# Graduation_Project.net
KiCad netlist of a schematic drawn in EAGLE
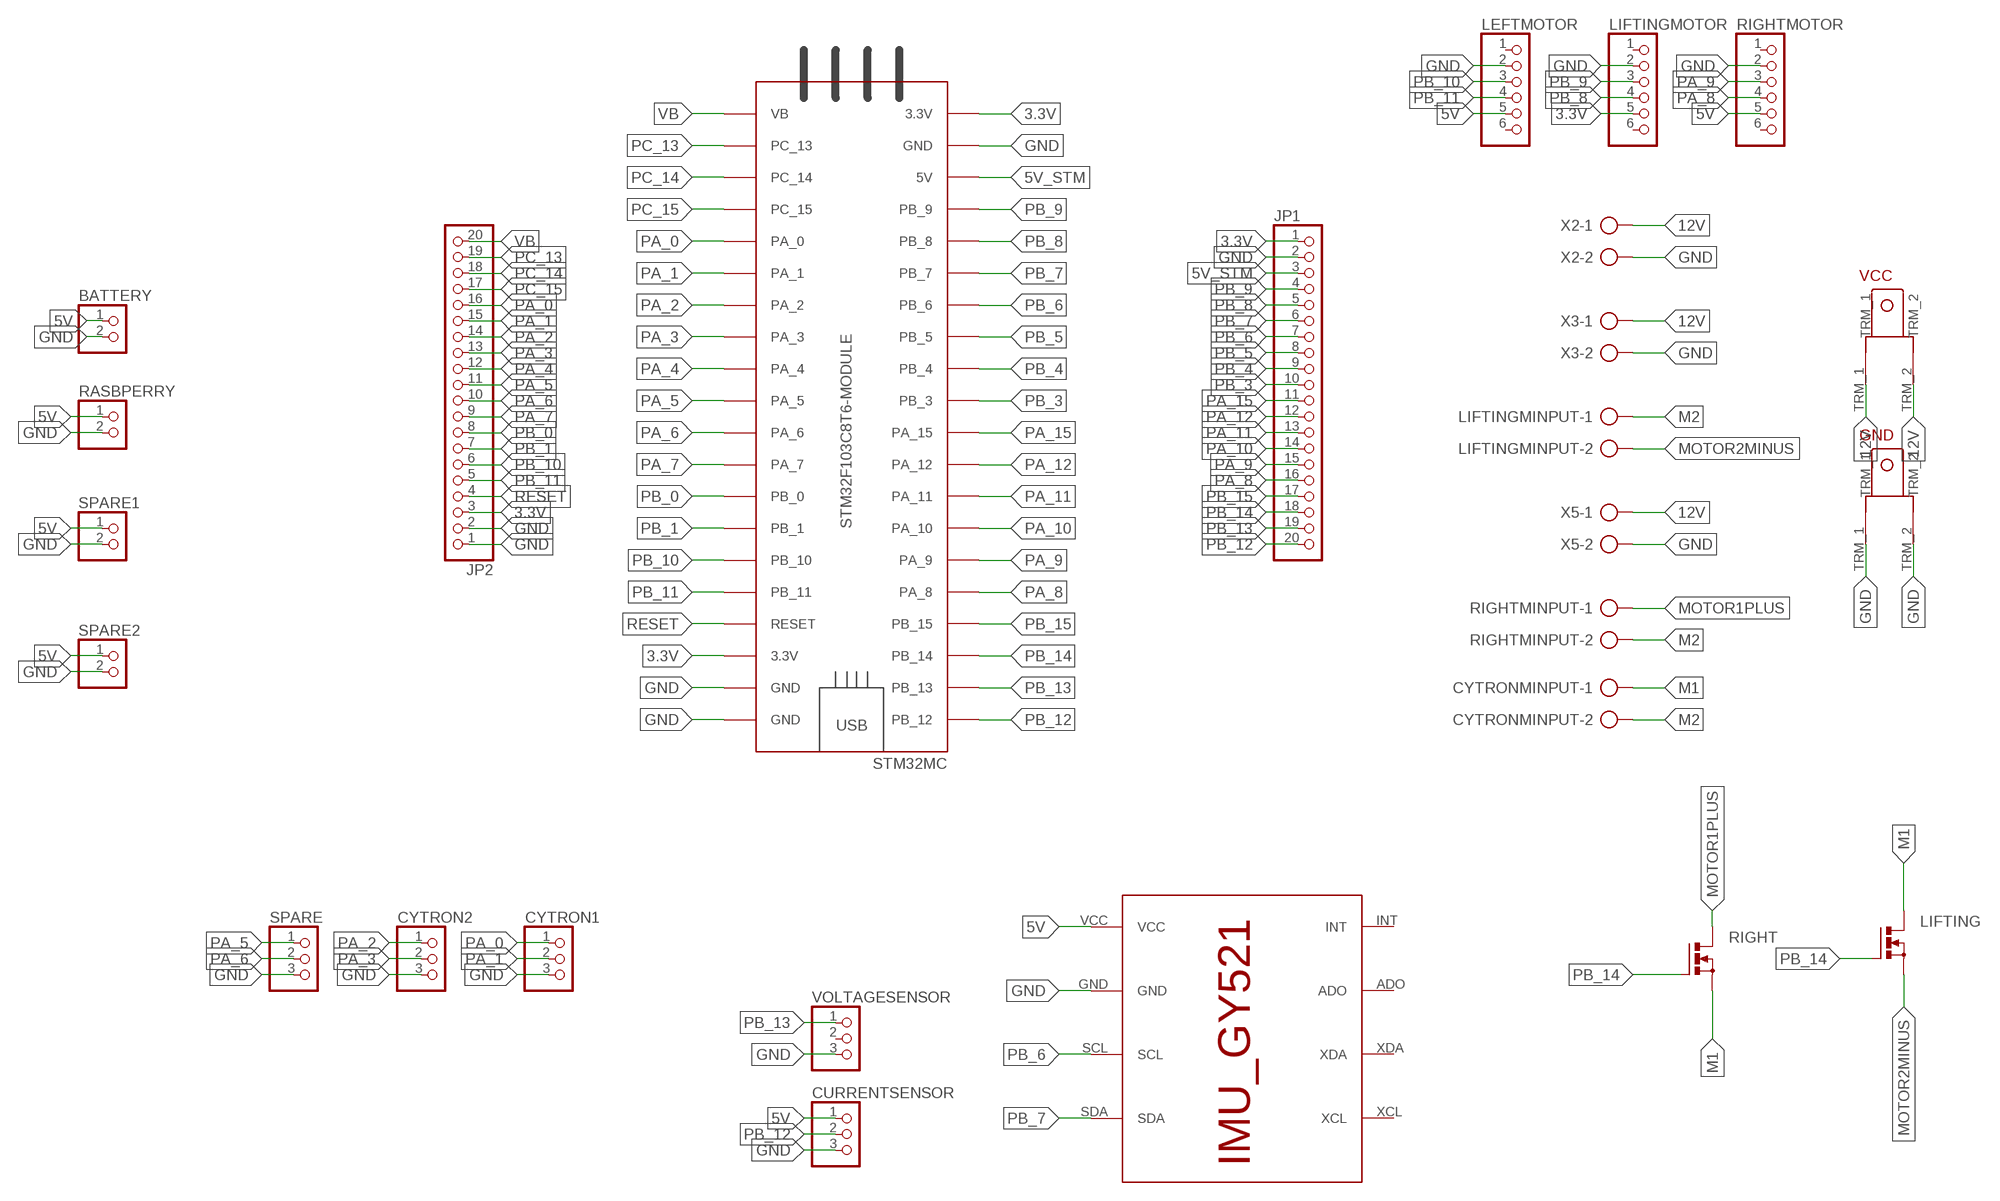
[diagram p0: schematic, sheet 1]

(export (version "E")
  (design (tool "Eeschema 10.0.6"))
  (components
    (comp (ref "BATTERY")
      (value "PINHD-1X2")
      (footprint "eagle-import:1X02")
      (libsource (lib "eagle-import") (part "PINHD-1X2"))
    )
    (comp (ref "CURRENTSENSOR")
      (value "PINHD-1X3")
      (footprint "eagle-import:1X03")
      (libsource (lib "eagle-import") (part "PINHD-1X3"))
    )
    (comp (ref "CYTRON1")
      (value "PINHD-1X3")
      (footprint "eagle-import:1X03")
      (libsource (lib "eagle-import") (part "PINHD-1X3"))
    )
    (comp (ref "CYTRON2")
      (value "PINHD-1X3")
      (footprint "eagle-import:1X03")
      (libsource (lib "eagle-import") (part "PINHD-1X3"))
    )
    (comp (ref "CYTRONMINPUT")
      (value "AK300/2")
      (footprint "eagle-import:AK300_2")
      (libsource (lib "eagle-import") (part "AK300/2"))
    )
    (comp (ref "GND")
      (value "TERMINAL_EDITED")
      (footprint "eagle-import:TERMINAL_EDITED")
      (libsource (lib "eagle-import") (part "TERMINAL_EDITED"))
    )
    (comp (ref "JP1")
      (value "PINHD-1X20")
      (footprint "eagle-import:1X20")
      (libsource (lib "eagle-import") (part "PINHD-1X20"))
    )
    (comp (ref "JP2")
      (value "PINHD-1X20")
      (footprint "eagle-import:1X20")
      (libsource (lib "eagle-import") (part "PINHD-1X20"))
    )
    (comp (ref "LEFTMOTOR")
      (value "PINHD-1X6")
      (footprint "eagle-import:1X06")
      (libsource (lib "eagle-import") (part "PINHD-1X6"))
    )
    (comp (ref "LIFTING")
      (value "MOSFET_NTO220BH")
      (footprint "eagle-import:TO220BH")
      (libsource (lib "eagle-import") (part "MOSFET_NTO220BH"))
    )
    (comp (ref "LIFTINGMINPUT")
      (value "AK300/2")
      (footprint "eagle-import:AK300_2")
      (libsource (lib "eagle-import") (part "AK300/2"))
    )
    (comp (ref "LIFTINGMOTOR")
      (value "PINHD-1X6")
      (footprint "eagle-import:1X06")
      (libsource (lib "eagle-import") (part "PINHD-1X6"))
    )
    (comp (ref "RASBPERRY")
      (value "PINHD-1X2")
      (footprint "eagle-import:1X02")
      (libsource (lib "eagle-import") (part "PINHD-1X2"))
    )
    (comp (ref "RIGHT")
      (value "MOSFET_NTO220BH")
      (footprint "eagle-import:TO220BH")
      (libsource (lib "eagle-import") (part "MOSFET_NTO220BH"))
    )
    (comp (ref "RIGHTMINPUT")
      (value "AK300/2")
      (footprint "eagle-import:AK300_2")
      (libsource (lib "eagle-import") (part "AK300/2"))
    )
    (comp (ref "RIGHTMOTOR")
      (value "PINHD-1X6")
      (footprint "eagle-import:1X06")
      (libsource (lib "eagle-import") (part "PINHD-1X6"))
    )
    (comp (ref "SPARE")
      (value "PINHD-1X3")
      (footprint "eagle-import:1X03")
      (libsource (lib "eagle-import") (part "PINHD-1X3"))
    )
    (comp (ref "SPARE1")
      (value "PINHD-1X2")
      (footprint "eagle-import:1X02")
      (libsource (lib "eagle-import") (part "PINHD-1X2"))
    )
    (comp (ref "SPARE2")
      (value "PINHD-1X2")
      (footprint "eagle-import:1X02")
      (libsource (lib "eagle-import") (part "PINHD-1X2"))
    )
    (comp (ref "STM32MC")
      (value "STM32F103C8T6-MODULE")
      (footprint "eagle-import:STM32F103C8T6-MODULE")
      (libsource (lib "eagle-import") (part "STM32F103C8T6-MODULE"))
    )
    (comp (ref "U$1")
      (value "IMU_ROBOCON_GY521")
      (footprint "eagle-import:IMU_GY521")
      (libsource (lib "eagle-import") (part "IMU_ROBOCON_GY521"))
    )
    (comp (ref "VCC")
      (value "TERMINAL_EDITED")
      (footprint "eagle-import:TERMINAL_EDITED")
      (libsource (lib "eagle-import") (part "TERMINAL_EDITED"))
    )
    (comp (ref "VOLTAGESENSOR")
      (value "PINHD-1X3")
      (footprint "eagle-import:1X03")
      (libsource (lib "eagle-import") (part "PINHD-1X3"))
    )
    (comp (ref "X2")
      (value "AK300/2")
      (footprint "eagle-import:AK300_2")
      (libsource (lib "eagle-import") (part "AK300/2"))
    )
    (comp (ref "X3")
      (value "AK300/2")
      (footprint "eagle-import:AK300_2")
      (libsource (lib "eagle-import") (part "AK300/2"))
    )
    (comp (ref "X5")
      (value "AK300/2")
      (footprint "eagle-import:AK300_2")
      (libsource (lib "eagle-import") (part "AK300/2"))
    )
  )
  (nets
    (net (code "1") (name "3.3V") (class "Default")
      (node (ref "JP1") (pin "1") (pinfunction "1_1") (pintype "passive"))
      (node (ref "JP2") (pin "3") (pinfunction "3_3") (pintype "passive"))
      (node (ref "LIFTINGMOTOR") (pin "5") (pinfunction "5_5") (pintype "passive"))
      (node (ref "STM32MC") (pin "3.3V_1") (pinfunction "3.3V_3.3V_1") (pintype "bidirectional"))
      (node (ref "STM32MC") (pin "3.3V_2") (pinfunction "3.3V_3.3V_2") (pintype "bidirectional"))
    )
    (net (code "2") (name "5V") (class "Default")
      (node (ref "BATTERY") (pin "1") (pinfunction "1_1") (pintype "passive"))
      (node (ref "CURRENTSENSOR") (pin "1") (pinfunction "1_1") (pintype "passive"))
      (node (ref "LEFTMOTOR") (pin "5") (pinfunction "5_5") (pintype "passive"))
      (node (ref "RASBPERRY") (pin "1") (pinfunction "1_1") (pintype "passive"))
      (node (ref "RIGHTMOTOR") (pin "5") (pinfunction "5_5") (pintype "passive"))
      (node (ref "SPARE1") (pin "1") (pinfunction "1_1") (pintype "passive"))
      (node (ref "SPARE2") (pin "1") (pinfunction "1_1") (pintype "passive"))
      (node (ref "U$1") (pin "VCC") (pinfunction "VCC_VCC") (pintype "bidirectional"))
    )
    (net (code "3") (name "5V_STM") (class "Default")
      (node (ref "JP1") (pin "3") (pinfunction "3_3") (pintype "passive"))
      (node (ref "STM32MC") (pin "5V") (pinfunction "5V_5V") (pintype "bidirectional"))
    )
    (net (code "4") (name "12V") (class "Default")
      (node (ref "VCC") (pin "TRM_1") (pinfunction "TRM_1_TRM_1") (pintype "bidirectional"))
      (node (ref "VCC") (pin "TRM_2") (pinfunction "TRM_2_TRM_2") (pintype "bidirectional"))
      (node (ref "X2") (pin "1") (pinfunction "KL_1") (pintype "passive"))
      (node (ref "X3") (pin "1") (pinfunction "KL_1") (pintype "passive"))
      (node (ref "X5") (pin "1") (pinfunction "KL_1") (pintype "passive"))
    )
    (net (code "5") (name "GND") (class "Default")
      (node (ref "BATTERY") (pin "2") (pinfunction "2_2") (pintype "passive"))
      (node (ref "CURRENTSENSOR") (pin "3") (pinfunction "3_3") (pintype "passive"))
      (node (ref "CYTRON1") (pin "3") (pinfunction "3_3") (pintype "passive"))
      (node (ref "CYTRON2") (pin "3") (pinfunction "3_3") (pintype "passive"))
      (node (ref "GND") (pin "TRM_1") (pinfunction "TRM_1_TRM_1") (pintype "bidirectional"))
      (node (ref "GND") (pin "TRM_2") (pinfunction "TRM_2_TRM_2") (pintype "bidirectional"))
      (node (ref "JP1") (pin "2") (pinfunction "2_2") (pintype "passive"))
      (node (ref "JP2") (pin "1") (pinfunction "1_1") (pintype "passive"))
      (node (ref "JP2") (pin "2") (pinfunction "2_2") (pintype "passive"))
      (node (ref "LEFTMOTOR") (pin "2") (pinfunction "2_2") (pintype "passive"))
      (node (ref "LIFTINGMOTOR") (pin "2") (pinfunction "2_2") (pintype "passive"))
      (node (ref "RASBPERRY") (pin "2") (pinfunction "2_2") (pintype "passive"))
      (node (ref "RIGHTMOTOR") (pin "2") (pinfunction "2_2") (pintype "passive"))
      (node (ref "SPARE") (pin "3") (pinfunction "3_3") (pintype "passive"))
      (node (ref "SPARE1") (pin "2") (pinfunction "2_2") (pintype "passive"))
      (node (ref "SPARE2") (pin "2") (pinfunction "2_2") (pintype "passive"))
      (node (ref "STM32MC") (pin "GND_1") (pinfunction "GND_GND_1") (pintype "bidirectional"))
      (node (ref "STM32MC") (pin "GND_2") (pinfunction "GND_GND_2") (pintype "bidirectional"))
      (node (ref "STM32MC") (pin "GND_3") (pinfunction "GND_GND_3") (pintype "power_in"))
      (node (ref "U$1") (pin "GND") (pinfunction "GND_GND") (pintype "bidirectional"))
      (node (ref "VOLTAGESENSOR") (pin "3") (pinfunction "3_3") (pintype "passive"))
      (node (ref "X2") (pin "2") (pinfunction "KL_2") (pintype "passive"))
      (node (ref "X3") (pin "2") (pinfunction "KL_2") (pintype "passive"))
      (node (ref "X5") (pin "2") (pinfunction "KL_2") (pintype "passive"))
    )
    (net (code "6") (name "M1") (class "Default")
      (node (ref "CYTRONMINPUT") (pin "1") (pinfunction "KL_1") (pintype "passive"))
      (node (ref "LIFTING") (pin "D") (pinfunction "D_D") (pintype "passive"))
      (node (ref "RIGHT") (pin "S") (pinfunction "S_S") (pintype "passive"))
    )
    (net (code "7") (name "M2") (class "Default")
      (node (ref "CYTRONMINPUT") (pin "2") (pinfunction "KL_2") (pintype "passive"))
      (node (ref "LIFTINGMINPUT") (pin "1") (pinfunction "KL_1") (pintype "passive"))
      (node (ref "RIGHTMINPUT") (pin "2") (pinfunction "KL_2") (pintype "passive"))
    )
    (net (code "8") (name "MOTOR1PLUS") (class "Default")
      (node (ref "RIGHT") (pin "D") (pinfunction "D_D") (pintype "passive"))
      (node (ref "RIGHTMINPUT") (pin "1") (pinfunction "KL_1") (pintype "passive"))
    )
    (net (code "9") (name "MOTOR2MINUS") (class "Default")
      (node (ref "LIFTING") (pin "S") (pinfunction "S_S") (pintype "passive"))
      (node (ref "LIFTINGMINPUT") (pin "2") (pinfunction "KL_2") (pintype "passive"))
    )
    (net (code "10") (name "PA_0") (class "Default")
      (node (ref "CYTRON1") (pin "1") (pinfunction "1_1") (pintype "passive"))
      (node (ref "JP2") (pin "16") (pinfunction "16_16") (pintype "passive"))
      (node (ref "STM32MC") (pin "PA_0") (pinfunction "PA_0_PA_0") (pintype "bidirectional"))
    )
    (net (code "11") (name "PA_1") (class "Default")
      (node (ref "CYTRON1") (pin "2") (pinfunction "2_2") (pintype "passive"))
      (node (ref "JP2") (pin "15") (pinfunction "15_15") (pintype "passive"))
      (node (ref "STM32MC") (pin "PA_1") (pinfunction "PA_1_PA_1") (pintype "bidirectional"))
    )
    (net (code "12") (name "PA_2") (class "Default")
      (node (ref "CYTRON2") (pin "1") (pinfunction "1_1") (pintype "passive"))
      (node (ref "JP2") (pin "14") (pinfunction "14_14") (pintype "passive"))
      (node (ref "STM32MC") (pin "PA_2") (pinfunction "PA_2_PA_2") (pintype "bidirectional"))
    )
    (net (code "13") (name "PA_3") (class "Default")
      (node (ref "CYTRON2") (pin "2") (pinfunction "2_2") (pintype "passive"))
      (node (ref "JP2") (pin "13") (pinfunction "13_13") (pintype "passive"))
      (node (ref "STM32MC") (pin "PA_3") (pinfunction "PA_3_PA_3") (pintype "bidirectional"))
    )
    (net (code "14") (name "PA_4") (class "Default")
      (node (ref "JP2") (pin "12") (pinfunction "12_12") (pintype "passive"))
      (node (ref "STM32MC") (pin "PA_4") (pinfunction "PA_4_PA_4") (pintype "bidirectional"))
    )
    (net (code "15") (name "PA_5") (class "Default")
      (node (ref "JP2") (pin "11") (pinfunction "11_11") (pintype "passive"))
      (node (ref "SPARE") (pin "1") (pinfunction "1_1") (pintype "passive"))
      (node (ref "STM32MC") (pin "PA_5") (pinfunction "PA_5_PA_5") (pintype "bidirectional"))
    )
    (net (code "16") (name "PA_6") (class "Default")
      (node (ref "JP2") (pin "10") (pinfunction "10_10") (pintype "passive"))
      (node (ref "SPARE") (pin "2") (pinfunction "2_2") (pintype "passive"))
      (node (ref "STM32MC") (pin "PA_6") (pinfunction "PA_6_PA_6") (pintype "bidirectional"))
    )
    (net (code "17") (name "PA_7") (class "Default")
      (node (ref "JP2") (pin "9") (pinfunction "9_9") (pintype "passive"))
      (node (ref "STM32MC") (pin "PA_7") (pinfunction "PA_7_PA_7") (pintype "bidirectional"))
    )
    (net (code "18") (name "PA_8") (class "Default")
      (node (ref "JP1") (pin "16") (pinfunction "16_16") (pintype "passive"))
      (node (ref "RIGHTMOTOR") (pin "4") (pinfunction "4_4") (pintype "passive"))
      (node (ref "STM32MC") (pin "PA_8") (pinfunction "PA_8_PA_8") (pintype "bidirectional"))
    )
    (net (code "19") (name "PA_9") (class "Default")
      (node (ref "JP1") (pin "15") (pinfunction "15_15") (pintype "passive"))
      (node (ref "RIGHTMOTOR") (pin "3") (pinfunction "3_3") (pintype "passive"))
      (node (ref "STM32MC") (pin "PA_9") (pinfunction "PA_9_PA_9") (pintype "bidirectional"))
    )
    (net (code "20") (name "PA_10") (class "Default")
      (node (ref "JP1") (pin "14") (pinfunction "14_14") (pintype "passive"))
      (node (ref "STM32MC") (pin "PA_10") (pinfunction "PA_10_PA_10") (pintype "bidirectional"))
    )
    (net (code "21") (name "PA_11") (class "Default")
      (node (ref "JP1") (pin "13") (pinfunction "13_13") (pintype "passive"))
      (node (ref "STM32MC") (pin "PA_11") (pinfunction "PA_11_PA_11") (pintype "bidirectional"))
    )
    (net (code "22") (name "PA_12") (class "Default")
      (node (ref "JP1") (pin "12") (pinfunction "12_12") (pintype "passive"))
      (node (ref "STM32MC") (pin "PA_12") (pinfunction "PA_12_PA_12") (pintype "bidirectional"))
    )
    (net (code "23") (name "PA_15") (class "Default")
      (node (ref "JP1") (pin "11") (pinfunction "11_11") (pintype "passive"))
      (node (ref "STM32MC") (pin "PA_15") (pinfunction "PA_15_PA_15") (pintype "bidirectional"))
    )
    (net (code "24") (name "PB_0") (class "Default")
      (node (ref "JP2") (pin "8") (pinfunction "8_8") (pintype "passive"))
      (node (ref "STM32MC") (pin "PB_0") (pinfunction "PB_0_PB_0") (pintype "bidirectional"))
    )
    (net (code "25") (name "PB_1") (class "Default")
      (node (ref "JP2") (pin "7") (pinfunction "7_7") (pintype "passive"))
      (node (ref "STM32MC") (pin "PB_1") (pinfunction "PB_1_PB_1") (pintype "bidirectional"))
    )
    (net (code "26") (name "PB_3") (class "Default")
      (node (ref "JP1") (pin "10") (pinfunction "10_10") (pintype "passive"))
      (node (ref "STM32MC") (pin "PB_3") (pinfunction "PB_3_PB_3") (pintype "bidirectional"))
    )
    (net (code "27") (name "PB_4") (class "Default")
      (node (ref "JP1") (pin "9") (pinfunction "9_9") (pintype "passive"))
      (node (ref "STM32MC") (pin "PB_4") (pinfunction "PB_4_PB_4") (pintype "bidirectional"))
    )
    (net (code "28") (name "PB_5") (class "Default")
      (node (ref "JP1") (pin "8") (pinfunction "8_8") (pintype "passive"))
      (node (ref "STM32MC") (pin "PB_5") (pinfunction "PB_5_PB_5") (pintype "bidirectional"))
    )
    (net (code "29") (name "PB_6") (class "Default")
      (node (ref "JP1") (pin "7") (pinfunction "7_7") (pintype "passive"))
      (node (ref "STM32MC") (pin "PB_6") (pinfunction "PB_6_PB_6") (pintype "bidirectional"))
      (node (ref "U$1") (pin "SCL") (pinfunction "SCL_SCL") (pintype "bidirectional"))
    )
    (net (code "30") (name "PB_7") (class "Default")
      (node (ref "JP1") (pin "6") (pinfunction "6_6") (pintype "passive"))
      (node (ref "STM32MC") (pin "PB_7") (pinfunction "PB_7_PB_7") (pintype "bidirectional"))
      (node (ref "U$1") (pin "SDA") (pinfunction "SDA_SDA") (pintype "bidirectional"))
    )
    (net (code "31") (name "PB_8") (class "Default")
      (node (ref "JP1") (pin "5") (pinfunction "5_5") (pintype "passive"))
      (node (ref "LIFTINGMOTOR") (pin "4") (pinfunction "4_4") (pintype "passive"))
      (node (ref "STM32MC") (pin "PB_8") (pinfunction "PB_8_PB_8") (pintype "bidirectional"))
    )
    (net (code "32") (name "PB_9") (class "Default")
      (node (ref "JP1") (pin "4") (pinfunction "4_4") (pintype "passive"))
      (node (ref "LIFTINGMOTOR") (pin "3") (pinfunction "3_3") (pintype "passive"))
      (node (ref "STM32MC") (pin "PB_9") (pinfunction "PB_9_PB_9") (pintype "bidirectional"))
    )
    (net (code "33") (name "PB_10") (class "Default")
      (node (ref "JP2") (pin "6") (pinfunction "6_6") (pintype "passive"))
      (node (ref "LEFTMOTOR") (pin "3") (pinfunction "3_3") (pintype "passive"))
      (node (ref "STM32MC") (pin "PB_10") (pinfunction "PB_10_PB_10") (pintype "bidirectional"))
    )
    (net (code "34") (name "PB_11") (class "Default")
      (node (ref "JP2") (pin "5") (pinfunction "5_5") (pintype "passive"))
      (node (ref "LEFTMOTOR") (pin "4") (pinfunction "4_4") (pintype "passive"))
      (node (ref "STM32MC") (pin "PB_11") (pinfunction "PB_11_PB_11") (pintype "bidirectional"))
    )
    (net (code "35") (name "PB_12") (class "Default")
      (node (ref "CURRENTSENSOR") (pin "2") (pinfunction "2_2") (pintype "passive"))
      (node (ref "JP1") (pin "20") (pinfunction "20_20") (pintype "passive"))
      (node (ref "STM32MC") (pin "PB_12") (pinfunction "PB_12_PB_12") (pintype "bidirectional"))
    )
    (net (code "36") (name "PB_13") (class "Default")
      (node (ref "JP1") (pin "19") (pinfunction "19_19") (pintype "passive"))
      (node (ref "STM32MC") (pin "PB_13") (pinfunction "PB_13_PB_13") (pintype "bidirectional"))
      (node (ref "VOLTAGESENSOR") (pin "1") (pinfunction "1_1") (pintype "passive"))
    )
    (net (code "37") (name "PB_14") (class "Default")
      (node (ref "JP1") (pin "18") (pinfunction "18_18") (pintype "passive"))
      (node (ref "LIFTING") (pin "G") (pinfunction "G_G") (pintype "passive"))
      (node (ref "RIGHT") (pin "G") (pinfunction "G_G") (pintype "passive"))
      (node (ref "STM32MC") (pin "PB_14") (pinfunction "PB_14_PB_14") (pintype "bidirectional"))
    )
    (net (code "38") (name "PB_15") (class "Default")
      (node (ref "JP1") (pin "17") (pinfunction "17_17") (pintype "passive"))
      (node (ref "STM32MC") (pin "PB_15") (pinfunction "PB_15_PB_15") (pintype "bidirectional"))
    )
    (net (code "39") (name "PC_13") (class "Default")
      (node (ref "JP2") (pin "19") (pinfunction "19_19") (pintype "passive"))
      (node (ref "STM32MC") (pin "PC_13") (pinfunction "PC_13_PC_13") (pintype "bidirectional"))
    )
    (net (code "40") (name "PC_14") (class "Default")
      (node (ref "JP2") (pin "18") (pinfunction "18_18") (pintype "passive"))
      (node (ref "STM32MC") (pin "PC_14") (pinfunction "PC_14_PC_14") (pintype "bidirectional"))
    )
    (net (code "41") (name "PC_15") (class "Default")
      (node (ref "JP2") (pin "17") (pinfunction "17_17") (pintype "passive"))
      (node (ref "STM32MC") (pin "PC_15") (pinfunction "PC_15_PC_15") (pintype "bidirectional"))
    )
    (net (code "42") (name "RESET") (class "Default")
      (node (ref "JP2") (pin "4") (pinfunction "4_4") (pintype "passive"))
      (node (ref "STM32MC") (pin "RESET") (pinfunction "RESET_RESET") (pintype "bidirectional"))
    )
    (net (code "43") (name "VB") (class "Default")
      (node (ref "JP2") (pin "20") (pinfunction "20_20") (pintype "passive"))
      (node (ref "STM32MC") (pin "VB") (pinfunction "VB_VB") (pintype "bidirectional"))
    )
    (net (code "44") (name "unconnected-(LEFTMOTOR-Pad1)") (class "Default")
      (node (ref "LEFTMOTOR") (pin "1") (pinfunction "1_1") (pintype "passive"))
    )
    (net (code "45") (name "unconnected-(LEFTMOTOR-Pad6)") (class "Default")
      (node (ref "LEFTMOTOR") (pin "6") (pinfunction "6_6") (pintype "passive"))
    )
    (net (code "46") (name "unconnected-(LIFTINGMOTOR-Pad1)") (class "Default")
      (node (ref "LIFTINGMOTOR") (pin "1") (pinfunction "1_1") (pintype "passive"))
    )
    (net (code "47") (name "unconnected-(LIFTINGMOTOR-Pad6)") (class "Default")
      (node (ref "LIFTINGMOTOR") (pin "6") (pinfunction "6_6") (pintype "passive"))
    )
    (net (code "48") (name "unconnected-(RIGHTMOTOR-Pad1)") (class "Default")
      (node (ref "RIGHTMOTOR") (pin "1") (pinfunction "1_1") (pintype "passive"))
    )
    (net (code "49") (name "unconnected-(RIGHTMOTOR-Pad6)") (class "Default")
      (node (ref "RIGHTMOTOR") (pin "6") (pinfunction "6_6") (pintype "passive"))
    )
    (net (code "50") (name "unconnected-(U$1-PadADO)") (class "Default")
      (node (ref "U$1") (pin "ADO") (pinfunction "ADO_ADO") (pintype "bidirectional"))
    )
    (net (code "51") (name "unconnected-(U$1-PadINT)") (class "Default")
      (node (ref "U$1") (pin "INT") (pinfunction "INT_INT") (pintype "bidirectional"))
    )
    (net (code "52") (name "unconnected-(U$1-PadXCL)") (class "Default")
      (node (ref "U$1") (pin "XCL") (pinfunction "XCL_XCL") (pintype "bidirectional"))
    )
    (net (code "53") (name "unconnected-(U$1-PadXDA)") (class "Default")
      (node (ref "U$1") (pin "XDA") (pinfunction "XDA_XDA") (pintype "bidirectional"))
    )
    (net (code "54") (name "unconnected-(VOLTAGESENSOR-Pad2)") (class "Default")
      (node (ref "VOLTAGESENSOR") (pin "2") (pinfunction "2_2") (pintype "passive"))
    )
  )
)
